# 1-Schematic_Smart_Home.net
KiCad netlist of a schematic drawn in EasyEDA
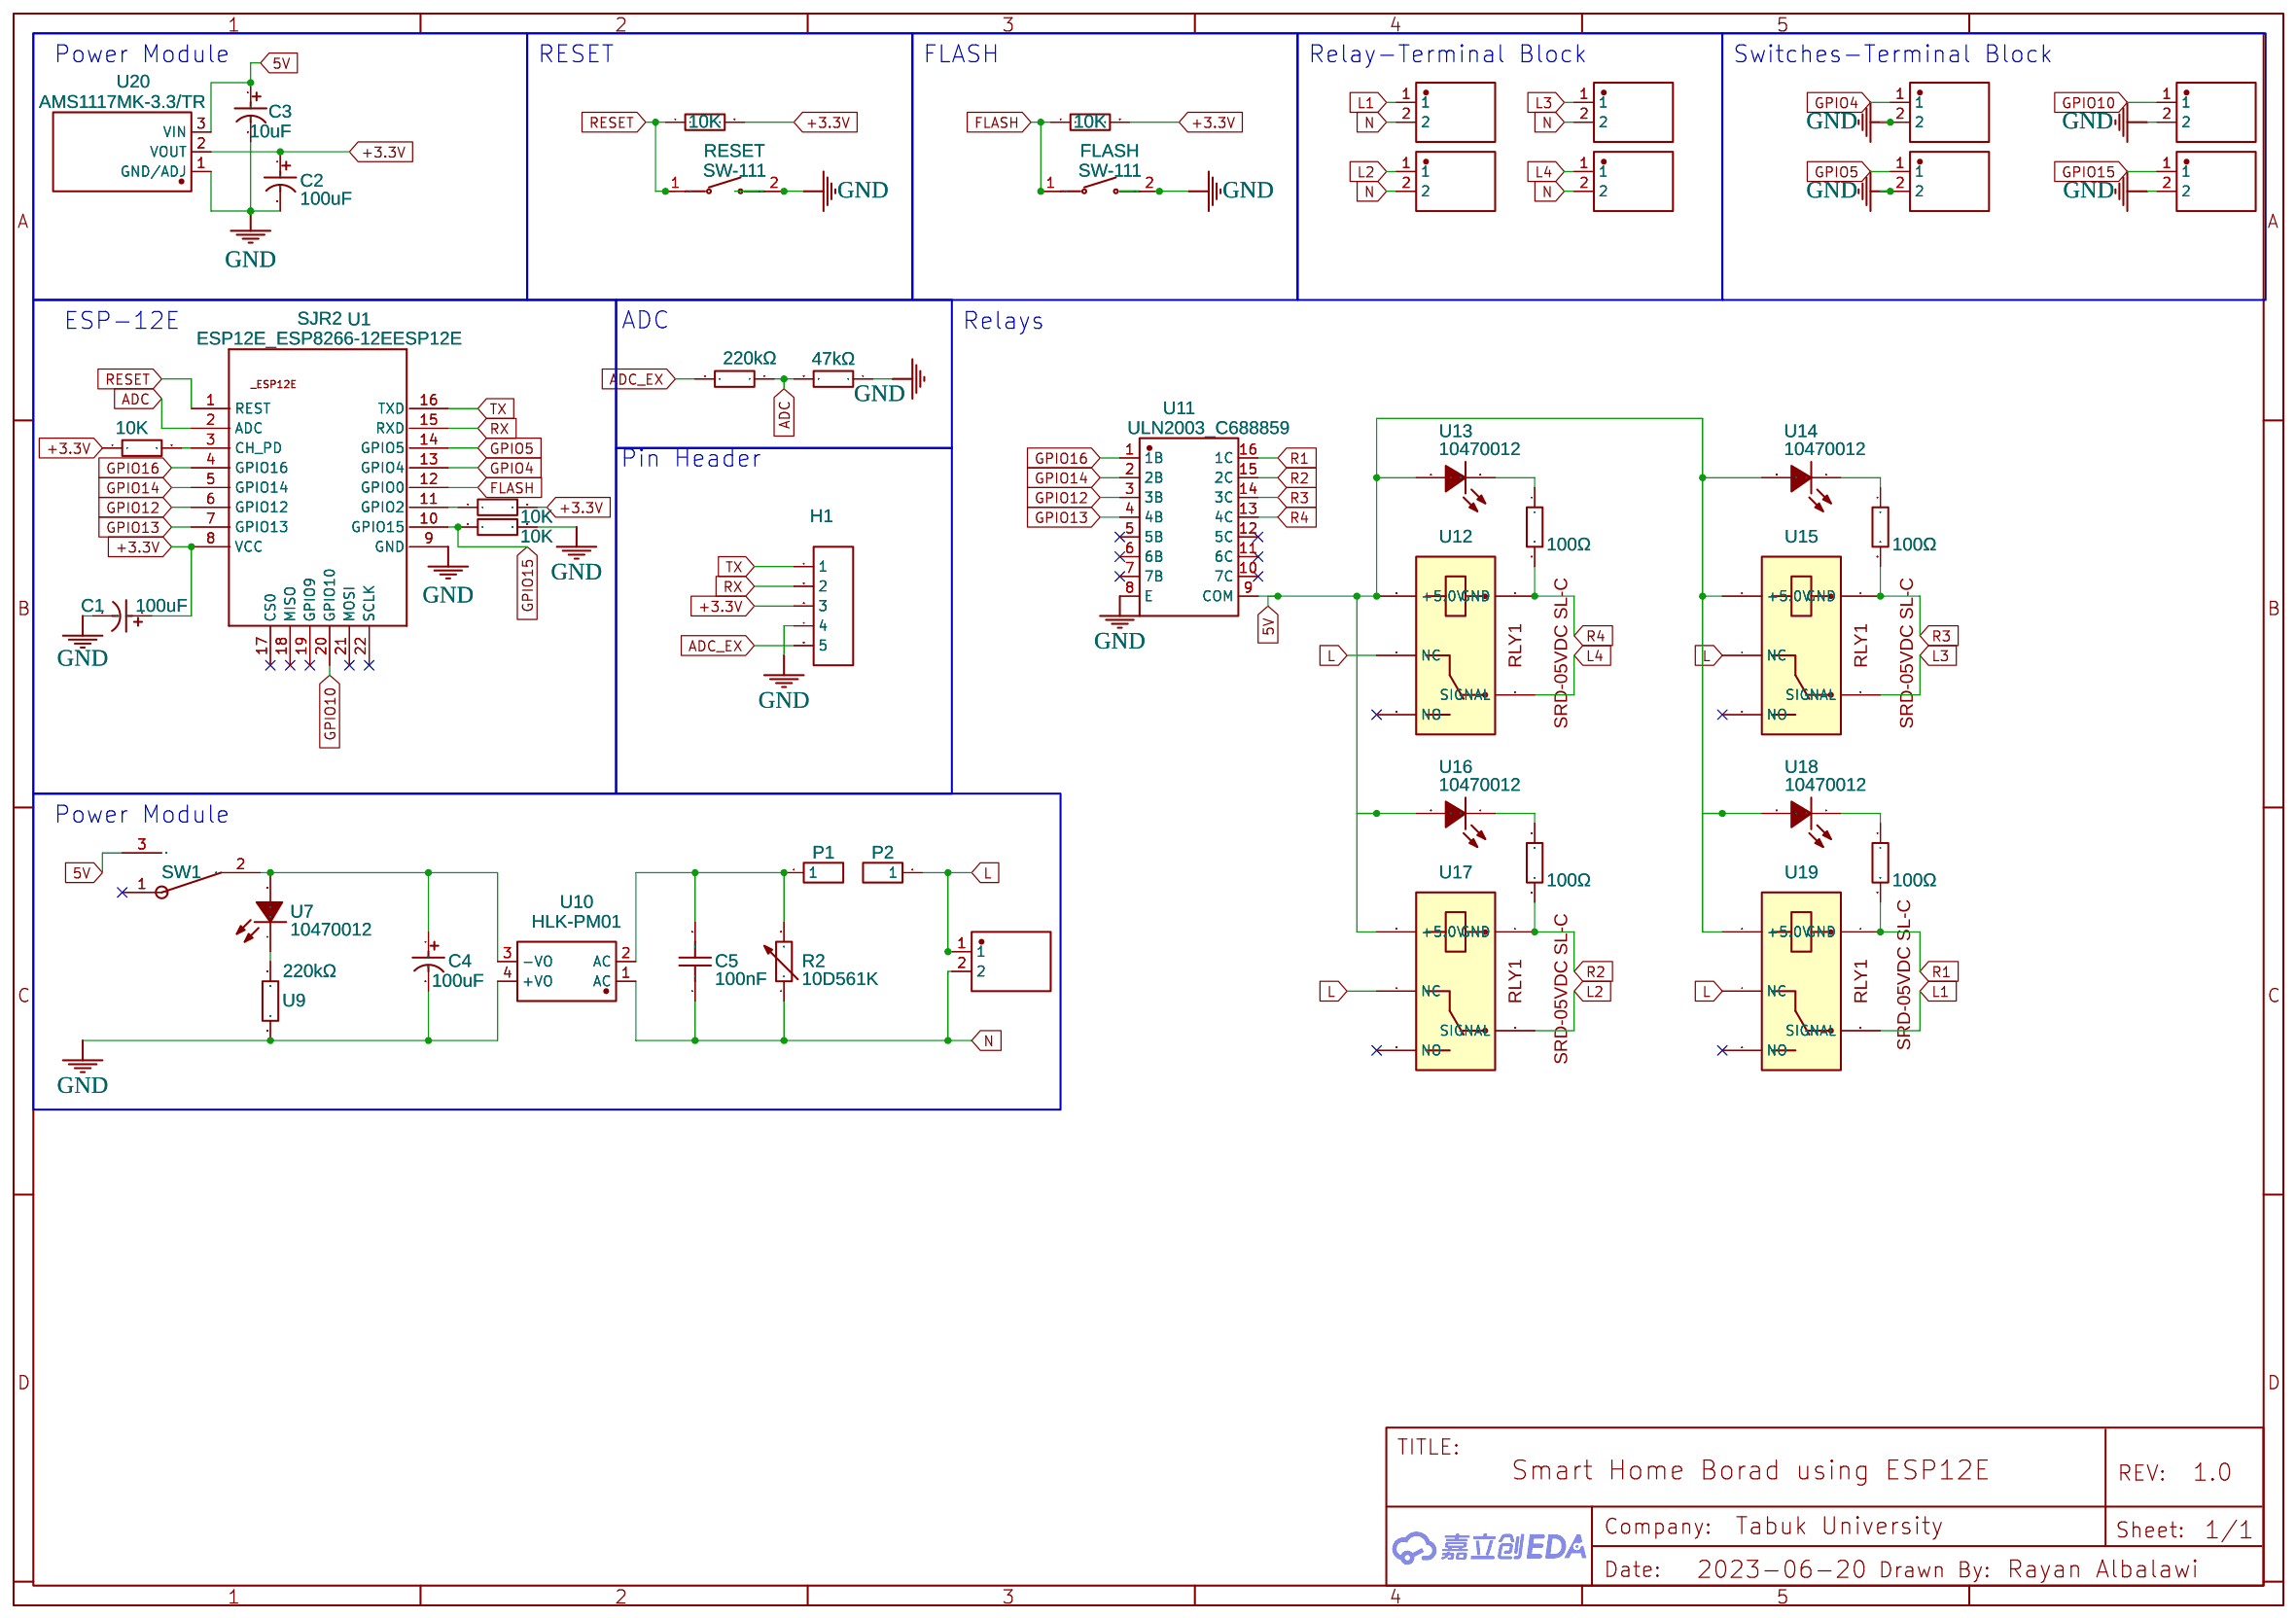
[diagram p0: schematic sheet]

(export (version "E")
  (design (tool "Eeschema 10.0.6"))
  (components
    (comp (ref "C1")
      (value "100uF")
      (fields
        (field (name "BOM_Manufacturer Part") "100uF 35V 6.3*11")
        (field (name "BOM_Supplier Part") "C45076")
      )
      (libsource (lib "") (part "100uF 35V 6.3*11_C45076_1"))
    )
    (comp (ref "C2")
      (value "100uF")
      (fields
        (field (name "BOM_Manufacturer Part") "100uF 35V 6.3*11")
        (field (name "BOM_Supplier Part") "C45076")
      )
      (libsource (lib "") (part "100uF 35V 6.3*11_C45076"))
    )
    (comp (ref "C3")
      (value "10uF")
      (fields
        (field (name "BOM_Manufacturer Part") "100uF 35V 6.3*11")
        (field (name "BOM_Supplier Part") "C45076")
      )
      (libsource (lib "") (part "100uF 35V 6.3*11_C45076"))
    )
    (comp (ref "C4")
      (value "100uF")
      (fields
        (field (name "BOM_Manufacturer Part") "100uF 35V 6.3*11")
        (field (name "BOM_Supplier Part") "C45076")
      )
      (libsource (lib "") (part "100uF 35V 6.3*11_C45076"))
    )
    (comp (ref "C5")
      (value "100nF")
      (fields
        (field (name "BOM_Manufacturer Part") "B32520C3104K000")
        (field (name "BOM_Supplier Part") "C125382")
      )
      (libsource (lib "") (part "B32520C3104K000"))
    )
    (comp (ref "CN1")
      (value "WJ127-5.0-2P_C187897")
      (fields
        (field (name "BOM_Manufacturer Part") "WJ127-5.0-2P")
        (field (name "BOM_Supplier Part") "C187897")
      )
      (libsource (lib "") (part "WJ127-5.0-2P_C187897"))
    )
    (comp (ref "CN2")
      (value "WJ127-5.0-2P_C187897")
      (fields
        (field (name "BOM_Manufacturer Part") "WJ127-5.0-2P")
        (field (name "BOM_Supplier Part") "C187897")
      )
      (libsource (lib "") (part "WJ127-5.0-2P_C187897"))
    )
    (comp (ref "CN3")
      (value "WJ127-5.0-2P_C187897")
      (fields
        (field (name "BOM_Manufacturer Part") "WJ127-5.0-2P")
        (field (name "BOM_Supplier Part") "C187897")
      )
      (libsource (lib "") (part "WJ127-5.0-2P_C187897"))
    )
    (comp (ref "CN4")
      (value "WJ127-5.0-2P_C187897")
      (fields
        (field (name "BOM_Manufacturer Part") "WJ127-5.0-2P")
        (field (name "BOM_Supplier Part") "C187897")
      )
      (libsource (lib "") (part "WJ127-5.0-2P_C187897"))
    )
    (comp (ref "CN5")
      (value "WJ127-5.0-2P_C187897")
      (fields
        (field (name "BOM_Manufacturer Part") "WJ127-5.0-2P")
        (field (name "BOM_Supplier Part") "C187897")
      )
      (libsource (lib "") (part "WJ127-5.0-2P_C187897"))
    )
    (comp (ref "CN6")
      (value "WJ127-5.0-2P_C187897")
      (fields
        (field (name "BOM_Manufacturer Part") "WJ127-5.0-2P")
        (field (name "BOM_Supplier Part") "C187897")
      )
      (libsource (lib "") (part "WJ127-5.0-2P_C187897"))
    )
    (comp (ref "CN7")
      (value "WJ127-5.0-2P_C187897")
      (fields
        (field (name "BOM_Manufacturer Part") "WJ127-5.0-2P")
        (field (name "BOM_Supplier Part") "C187897")
      )
      (libsource (lib "") (part "WJ127-5.0-2P_C187897"))
    )
    (comp (ref "CN8")
      (value "WJ127-5.0-2P_C187897")
      (fields
        (field (name "BOM_Manufacturer Part") "WJ127-5.0-2P")
        (field (name "BOM_Supplier Part") "C187897")
      )
      (libsource (lib "") (part "WJ127-5.0-2P_C187897"))
    )
    (comp (ref "CN9")
      (value "WJ127-5.0-2P_C187897")
      (fields
        (field (name "BOM_Manufacturer Part") "WJ127-5.0-2P")
        (field (name "BOM_Supplier Part") "C187897")
      )
      (libsource (lib "") (part "WJ127-5.0-2P_C187897"))
    )
    (comp (ref "FLASH")
      (value "SW-111")
      (fields (field (name "BOM_Supplier Part") "C294475"))
      (libsource (lib "") (part "SW-111"))
    )
    (comp (ref "H1")
      (value "Header-Female-2.54_1x5")
      (fields (field (name "BOM_Manufacturer Part") "2.54-1*5P母") (field (name "BOM_Supplier Part") "C50950"))
      (libsource (lib "") (part "Header-Female-2.54_1x5"))
    )
    (comp (ref "P1")
      (value "Header-Male-2.54_1x1")
      (fields (field (name "BOM_Manufacturer Part") "2.54-1*1P针") (field (name "BOM_Supplier Part") "C81276"))
      (libsource (lib "") (part "Header-Male-2.54_1x1"))
    )
    (comp (ref "P2")
      (value "Header-Male-2.54_1x1")
      (fields (field (name "BOM_Manufacturer Part") "2.54-1*1P针") (field (name "BOM_Supplier Part") "C81276"))
      (libsource (lib "") (part "Header-Male-2.54_1x1_1"))
    )
    (comp (ref "R1")
      (value "47kΩ")
      (fields
        (field (name "BOM_Manufacturer Part") "MOF2WS-47KΩ±5% T")
        (field (name "BOM_Supplier Part") "C121703")
      )
      (libsource (lib "") (part "MOF2WS-47KΩ±5% T_1"))
    )
    (comp (ref "R2")
      (value "10D561K")
      (fields (field (name "BOM_Supplier Part") "C113236"))
      (libsource (lib "") (part "10D561K"))
    )
    (comp (ref "R3")
      (value "100Ω")
      (fields
        (field (name "BOM_Manufacturer Part") "MOF2WS-47KΩ±5% T")
        (field (name "BOM_Supplier Part") "C121703")
      )
      (libsource (lib "") (part "MOF2WS-47KΩ±5% T"))
    )
    (comp (ref "R4")
      (value "100Ω")
      (fields
        (field (name "BOM_Manufacturer Part") "MOF2WS-47KΩ±5% T")
        (field (name "BOM_Supplier Part") "C121703")
      )
      (libsource (lib "") (part "MOF2WS-47KΩ±5% T"))
    )
    (comp (ref "R5")
      (value "100Ω")
      (fields
        (field (name "BOM_Manufacturer Part") "MOF2WS-47KΩ±5% T")
        (field (name "BOM_Supplier Part") "C121703")
      )
      (libsource (lib "") (part "MOF2WS-47KΩ±5% T"))
    )
    (comp (ref "R6")
      (value "100Ω")
      (fields
        (field (name "BOM_Manufacturer Part") "MOF2WS-47KΩ±5% T")
        (field (name "BOM_Supplier Part") "C121703")
      )
      (libsource (lib "") (part "MOF2WS-47KΩ±5% T"))
    )
    (comp (ref "RESET")
      (value "SW-111")
      (fields (field (name "BOM_Supplier Part") "C294475"))
      (libsource (lib "") (part "SW-111_1"))
    )
    (comp (ref "SJR2")
      (value "ESP12E_ESP8266-12EESP12E")
      (libsource (lib "") (part "ESP12E_ESP8266-12EESP12E"))
    )
    (comp (ref "SW1")
      (value "EG1218")
      (fields (field (name "BOM_Supplier Part") "C273394"))
      (libsource (lib "") (part "EG1218"))
    )
    (comp (ref "U1")
      (value "10K")
      (fields
        (field (name "BOM_Manufacturer Part") "B3950-10K 1%")
        (field (name "BOM_Supplier Part") "C9900005609")
      )
      (libsource (lib "") (part "B3950-10K 1%"))
    )
    (comp (ref "U3")
      (value "10K")
      (fields
        (field (name "BOM_Manufacturer Part") "B3950-10K 1%")
        (field (name "BOM_Supplier Part") "C9900005609")
      )
      (libsource (lib "") (part "B3950-10K 1%"))
    )
    (comp (ref "U4")
      (value "10K")
      (fields
        (field (name "BOM_Manufacturer Part") "B3950-10K 1%")
        (field (name "BOM_Supplier Part") "C9900005609")
      )
      (libsource (lib "") (part "B3950-10K 1%"))
    )
    (comp (ref "U5")
      (value "10K")
      (fields
        (field (name "BOM_Manufacturer Part") "B3950-10K 1%")
        (field (name "BOM_Supplier Part") "C9900005609")
      )
      (libsource (lib "") (part "B3950-10K 1%"))
    )
    (comp (ref "U6")
      (value "10K")
      (fields
        (field (name "BOM_Manufacturer Part") "B3950-10K 1%")
        (field (name "BOM_Supplier Part") "C9900005609")
      )
      (libsource (lib "") (part "B3950-10K 1%"))
    )
    (comp (ref "U7")
      (value "10470012")
      (fields (field (name "BOM_Supplier Part") "C9900018803"))
      (libsource (lib "") (part "10470012_1"))
    )
    (comp (ref "U8")
      (value "220kΩ")
      (fields
        (field (name "BOM_Manufacturer Part") "MOF3WS-100KΩ±5% T")
        (field (name "BOM_Supplier Part") "C121880")
      )
      (libsource (lib "") (part "MOF3WS-100KΩ±5% T"))
    )
    (comp (ref "U9")
      (value "220kΩ")
      (fields
        (field (name "BOM_Manufacturer Part") "MOF3WS-100KΩ±5% T")
        (field (name "BOM_Supplier Part") "C121880")
      )
      (libsource (lib "") (part "MOF3WS-100KΩ±5% T_1"))
    )
    (comp (ref "U10")
      (value "HLK-PM01")
      (fields (field (name "BOM_Supplier Part") "C209903"))
      (libsource (lib "") (part "HLK-PM01"))
    )
    (comp (ref "U11")
      (value "ULN2003_C688859")
      (fields (field (name "BOM_Manufacturer Part") "ULN2003") (field (name "BOM_Supplier Part") "C688859"))
      (libsource (lib "") (part "ULN2003_C688859"))
    )
    (comp (ref "U12")
      (value "SRD-05VDC SL-C BY JMAD COPY")
      (fields (field (name "BOM_Supplier Part") "SRD-05VDC SL-C"))
      (libsource (lib "") (part "SRD-05VDC SL-C BY JMAD COPY_1"))
    )
    (comp (ref "U13")
      (value "10470012")
      (fields (field (name "BOM_Supplier Part") "C9900018803"))
      (libsource (lib "") (part "10470012"))
    )
    (comp (ref "U14")
      (value "10470012")
      (fields (field (name "BOM_Supplier Part") "C9900018803"))
      (libsource (lib "") (part "10470012"))
    )
    (comp (ref "U15")
      (value "SRD-05VDC SL-C BY JMAD COPY")
      (fields (field (name "BOM_Supplier Part") "SRD-05VDC SL-C"))
      (libsource (lib "") (part "SRD-05VDC SL-C BY JMAD COPY_1"))
    )
    (comp (ref "U16")
      (value "10470012")
      (fields (field (name "BOM_Supplier Part") "C9900018803"))
      (libsource (lib "") (part "10470012"))
    )
    (comp (ref "U17")
      (value "SRD-05VDC SL-C BY JMAD COPY")
      (fields (field (name "BOM_Supplier Part") "SRD-05VDC SL-C"))
      (libsource (lib "") (part "SRD-05VDC SL-C BY JMAD COPY_1"))
    )
    (comp (ref "U18")
      (value "10470012")
      (fields (field (name "BOM_Supplier Part") "C9900018803"))
      (libsource (lib "") (part "10470012"))
    )
    (comp (ref "U19")
      (value "SRD-05VDC SL-C BY JMAD COPY")
      (fields (field (name "BOM_Supplier Part") "SRD-05VDC SL-C"))
      (libsource (lib "") (part "SRD-05VDC SL-C BY JMAD COPY"))
    )
    (comp (ref "U20")
      (value "AMS1117MK-3.3/TR")
      (fields (field (name "BOM_Supplier Part") "C498147"))
      (libsource (lib "") (part "AMS1117MK-3.3/TR"))
    )
  )
  (nets
    (net (code "1") (name "+3.3V") (class "Default")
      (node (ref "C1") (pin "1") (pinfunction "1_1") (pintype "input"))
      (node (ref "C2") (pin "1") (pinfunction "1_1") (pintype "input"))
      (node (ref "H1") (pin "3") (pinfunction "3_3") (pintype "input"))
      (node (ref "SJR2") (pin "8") (pinfunction "VCC_8") (pintype "bidirectional"))
      (node (ref "U1") (pin "1") (pinfunction "1_1") (pintype "unspecified"))
      (node (ref "U20") (pin "2") (pinfunction "VOUT_2") (pintype "unspecified"))
      (node (ref "U3") (pin "2") (pinfunction "2_2") (pintype "unspecified"))
      (node (ref "U5") (pin "2") (pinfunction "2_2") (pintype "unspecified"))
      (node (ref "U6") (pin "2") (pinfunction "2_2") (pintype "unspecified"))
    )
    (net (code "2") (name "5V") (class "Default")
      (node (ref "C3") (pin "1") (pinfunction "1_1") (pintype "input"))
      (node (ref "SW1") (pin "3") (pinfunction "3_3") (pintype "input"))
      (node (ref "U11") (pin "9") (pinfunction "COM_9") (pintype "unspecified"))
      (node (ref "U12") (pin "2") (pinfunction "+5.0V_2") (pintype "passive"))
      (node (ref "U13") (pin "2") (pinfunction "A_2") (pintype "unspecified"))
      (node (ref "U14") (pin "2") (pinfunction "A_2") (pintype "unspecified"))
      (node (ref "U15") (pin "2") (pinfunction "+5.0V_2") (pintype "passive"))
      (node (ref "U16") (pin "2") (pinfunction "A_2") (pintype "unspecified"))
      (node (ref "U17") (pin "2") (pinfunction "+5.0V_2") (pintype "passive"))
      (node (ref "U18") (pin "2") (pinfunction "A_2") (pintype "unspecified"))
      (node (ref "U19") (pin "2") (pinfunction "+5.0V_2") (pintype "passive"))
      (node (ref "U20") (pin "3") (pinfunction "VIN_3") (pintype "unspecified"))
    )
    (net (code "3") (name "ADC") (class "Default")
      (node (ref "R1") (pin "2") (pinfunction "2_2") (pintype "unspecified"))
      (node (ref "SJR2") (pin "2") (pinfunction "ADC_2") (pintype "bidirectional"))
      (node (ref "U8") (pin "1") (pinfunction "1_1") (pintype "unspecified"))
    )
    (net (code "4") (name "ADC_EX") (class "Default")
      (node (ref "H1") (pin "5") (pinfunction "5_5") (pintype "input"))
      (node (ref "U8") (pin "2") (pinfunction "2_2") (pintype "unspecified"))
    )
    (net (code "5") (name "FLASH") (class "Default")
      (node (ref "FLASH") (pin "1") (pinfunction "1_1") (pintype "unspecified"))
      (node (ref "SJR2") (pin "12") (pinfunction "GPIO0_12") (pintype "bidirectional"))
      (node (ref "U6") (pin "1") (pinfunction "1_1") (pintype "unspecified"))
    )
    (net (code "6") (name "GND") (class "Default")
      (node (ref "C1") (pin "2") (pinfunction "2_2") (pintype "input"))
      (node (ref "C2") (pin "2") (pinfunction "2_2") (pintype "input"))
      (node (ref "C3") (pin "2") (pinfunction "2_2") (pintype "input"))
      (node (ref "C4") (pin "2") (pinfunction "2_2") (pintype "input"))
      (node (ref "CN5") (pin "2") (pinfunction "2_2") (pintype "unspecified"))
      (node (ref "CN6") (pin "2") (pinfunction "2_2") (pintype "unspecified"))
      (node (ref "CN7") (pin "2") (pinfunction "2_2") (pintype "unspecified"))
      (node (ref "CN8") (pin "2") (pinfunction "2_2") (pintype "unspecified"))
      (node (ref "FLASH") (pin "2") (pinfunction "2_2") (pintype "unspecified"))
      (node (ref "H1") (pin "4") (pinfunction "4_4") (pintype "input"))
      (node (ref "R1") (pin "1") (pinfunction "1_1") (pintype "unspecified"))
      (node (ref "RESET") (pin "2") (pinfunction "2_2") (pintype "unspecified"))
      (node (ref "SJR2") (pin "9") (pinfunction "GND_9") (pintype "bidirectional"))
      (node (ref "U10") (pin "4") (pinfunction "+VO_4") (pintype "unspecified"))
      (node (ref "U11") (pin "8") (pinfunction "E_8") (pintype "unspecified"))
      (node (ref "U20") (pin "1") (pinfunction "GND/ADJ_1") (pintype "unspecified"))
      (node (ref "U4") (pin "2") (pinfunction "2_2") (pintype "unspecified"))
      (node (ref "U9") (pin "1") (pinfunction "1_1") (pintype "unspecified"))
    )
    (net (code "7") (name "GPIO4") (class "Default")
      (node (ref "CN8") (pin "1") (pinfunction "1_1") (pintype "unspecified"))
      (node (ref "SJR2") (pin "13") (pinfunction "GPIO4_13") (pintype "bidirectional"))
    )
    (net (code "8") (name "GPIO5") (class "Default")
      (node (ref "CN7") (pin "1") (pinfunction "1_1") (pintype "unspecified"))
      (node (ref "SJR2") (pin "14") (pinfunction "GPIO5_14") (pintype "bidirectional"))
    )
    (net (code "9") (name "GPIO10") (class "Default")
      (node (ref "CN6") (pin "1") (pinfunction "1_1") (pintype "unspecified"))
      (node (ref "SJR2") (pin "20") (pinfunction "GPIO10_20") (pintype "bidirectional"))
    )
    (net (code "10") (name "GPIO12") (class "Default")
      (node (ref "SJR2") (pin "6") (pinfunction "GPIO12_6") (pintype "bidirectional"))
      (node (ref "U11") (pin "3") (pinfunction "3B_3") (pintype "unspecified"))
    )
    (net (code "11") (name "GPIO13") (class "Default")
      (node (ref "SJR2") (pin "7") (pinfunction "GPIO13_7") (pintype "bidirectional"))
      (node (ref "U11") (pin "4") (pinfunction "4B_4") (pintype "unspecified"))
    )
    (net (code "12") (name "GPIO14") (class "Default")
      (node (ref "SJR2") (pin "5") (pinfunction "GPIO14_5") (pintype "bidirectional"))
      (node (ref "U11") (pin "2") (pinfunction "2B_2") (pintype "unspecified"))
    )
    (net (code "13") (name "GPIO15") (class "Default")
      (node (ref "CN5") (pin "1") (pinfunction "1_1") (pintype "unspecified"))
      (node (ref "SJR2") (pin "10") (pinfunction "GPIO15_10") (pintype "bidirectional"))
      (node (ref "U4") (pin "1") (pinfunction "1_1") (pintype "unspecified"))
    )
    (net (code "14") (name "GPIO16") (class "Default")
      (node (ref "SJR2") (pin "4") (pinfunction "GPIO16_4") (pintype "bidirectional"))
      (node (ref "U11") (pin "1") (pinfunction "1B_1") (pintype "unspecified"))
    )
    (net (code "15") (name "L") (class "Default")
      (node (ref "CN9") (pin "1") (pinfunction "1_1") (pintype "unspecified"))
      (node (ref "P2") (pin "1") (pinfunction "1_1") (pintype "input"))
      (node (ref "U12") (pin "4") (pinfunction "NC_4") (pintype "input"))
      (node (ref "U15") (pin "4") (pinfunction "NC_4") (pintype "input"))
      (node (ref "U17") (pin "4") (pinfunction "NC_4") (pintype "input"))
      (node (ref "U19") (pin "4") (pinfunction "NC_4") (pintype "input"))
    )
    (net (code "16") (name "L1") (class "Default")
      (node (ref "CN1") (pin "1") (pinfunction "1_1") (pintype "unspecified"))
      (node (ref "U19") (pin "5") (pinfunction "SIGNAL_5") (pintype "output"))
    )
    (net (code "17") (name "L2") (class "Default")
      (node (ref "CN2") (pin "1") (pinfunction "1_1") (pintype "unspecified"))
      (node (ref "U17") (pin "5") (pinfunction "SIGNAL_5") (pintype "output"))
    )
    (net (code "18") (name "L3") (class "Default")
      (node (ref "CN3") (pin "1") (pinfunction "1_1") (pintype "unspecified"))
      (node (ref "U15") (pin "5") (pinfunction "SIGNAL_5") (pintype "output"))
    )
    (net (code "19") (name "L4") (class "Default")
      (node (ref "CN4") (pin "1") (pinfunction "1_1") (pintype "unspecified"))
      (node (ref "U12") (pin "5") (pinfunction "SIGNAL_5") (pintype "output"))
    )
    (net (code "20") (name "N") (class "Default")
      (node (ref "C5") (pin "1") (pinfunction "1_1") (pintype "unspecified"))
      (node (ref "CN1") (pin "2") (pinfunction "2_2") (pintype "unspecified"))
      (node (ref "CN2") (pin "2") (pinfunction "2_2") (pintype "unspecified"))
      (node (ref "CN3") (pin "2") (pinfunction "2_2") (pintype "unspecified"))
      (node (ref "CN4") (pin "2") (pinfunction "2_2") (pintype "unspecified"))
      (node (ref "CN9") (pin "2") (pinfunction "2_2") (pintype "unspecified"))
      (node (ref "R2") (pin "1") (pinfunction "1_1") (pintype "unspecified"))
      (node (ref "U10") (pin "1") (pinfunction "AC_1") (pintype "unspecified"))
    )
    (net (code "21") (name "Net-(C5-Pad2)") (class "Default")
      (node (ref "C5") (pin "2") (pinfunction "2_2") (pintype "unspecified"))
      (node (ref "P1") (pin "1") (pinfunction "1_1") (pintype "input"))
      (node (ref "R2") (pin "2") (pinfunction "2_2") (pintype "unspecified"))
      (node (ref "U10") (pin "2") (pinfunction "AC_2") (pintype "unspecified"))
    )
    (net (code "22") (name "Net-(SJR2-CH_PD)") (class "Default")
      (node (ref "SJR2") (pin "3") (pinfunction "CH_PD_3") (pintype "bidirectional"))
      (node (ref "U1") (pin "2") (pinfunction "2_2") (pintype "unspecified"))
    )
    (net (code "23") (name "Net-(SJR2-GPIO2)") (class "Default")
      (node (ref "SJR2") (pin "11") (pinfunction "GPIO2_11") (pintype "bidirectional"))
      (node (ref "U3") (pin "1") (pinfunction "1_1") (pintype "unspecified"))
    )
    (net (code "24") (name "Net-(U7-K)") (class "Default")
      (node (ref "U7") (pin "1") (pinfunction "K_1") (pintype "unspecified"))
      (node (ref "U9") (pin "2") (pinfunction "2_2") (pintype "unspecified"))
    )
    (net (code "25") (name "Net-(U10--VO)") (class "Default")
      (node (ref "C4") (pin "1") (pinfunction "1_1") (pintype "input"))
      (node (ref "SW1") (pin "2") (pinfunction "2_2") (pintype "input"))
      (node (ref "U10") (pin "3") (pinfunction "-VO_3") (pintype "unspecified"))
      (node (ref "U7") (pin "2") (pinfunction "A_2") (pintype "unspecified"))
    )
    (net (code "26") (name "Net-(U13-K)") (class "Default")
      (node (ref "R3") (pin "1") (pinfunction "1_1") (pintype "unspecified"))
      (node (ref "U13") (pin "1") (pinfunction "K_1") (pintype "unspecified"))
    )
    (net (code "27") (name "Net-(U14-K)") (class "Default")
      (node (ref "R4") (pin "1") (pinfunction "1_1") (pintype "unspecified"))
      (node (ref "U14") (pin "1") (pinfunction "K_1") (pintype "unspecified"))
    )
    (net (code "28") (name "Net-(U16-K)") (class "Default")
      (node (ref "R5") (pin "1") (pinfunction "1_1") (pintype "unspecified"))
      (node (ref "U16") (pin "1") (pinfunction "K_1") (pintype "unspecified"))
    )
    (net (code "29") (name "Net-(U18-K)") (class "Default")
      (node (ref "R6") (pin "1") (pinfunction "1_1") (pintype "unspecified"))
      (node (ref "U18") (pin "1") (pinfunction "K_1") (pintype "unspecified"))
    )
    (net (code "30") (name "R1") (class "Default")
      (node (ref "R6") (pin "2") (pinfunction "2_2") (pintype "unspecified"))
      (node (ref "U11") (pin "16") (pinfunction "1C_16") (pintype "unspecified"))
      (node (ref "U19") (pin "1") (pinfunction "GND_1") (pintype "passive"))
    )
    (net (code "31") (name "R2") (class "Default")
      (node (ref "R5") (pin "2") (pinfunction "2_2") (pintype "unspecified"))
      (node (ref "U11") (pin "15") (pinfunction "2C_15") (pintype "unspecified"))
      (node (ref "U17") (pin "1") (pinfunction "GND_1") (pintype "passive"))
    )
    (net (code "32") (name "R3") (class "Default")
      (node (ref "R4") (pin "2") (pinfunction "2_2") (pintype "unspecified"))
      (node (ref "U11") (pin "14") (pinfunction "3C_14") (pintype "unspecified"))
      (node (ref "U15") (pin "1") (pinfunction "GND_1") (pintype "passive"))
    )
    (net (code "33") (name "R4") (class "Default")
      (node (ref "R3") (pin "2") (pinfunction "2_2") (pintype "unspecified"))
      (node (ref "U11") (pin "13") (pinfunction "4C_13") (pintype "unspecified"))
      (node (ref "U12") (pin "1") (pinfunction "GND_1") (pintype "passive"))
    )
    (net (code "34") (name "RESET") (class "Default")
      (node (ref "RESET") (pin "1") (pinfunction "1_1") (pintype "unspecified"))
      (node (ref "SJR2") (pin "1") (pinfunction "REST_1") (pintype "bidirectional"))
      (node (ref "U5") (pin "1") (pinfunction "1_1") (pintype "unspecified"))
    )
    (net (code "35") (name "RX") (class "Default")
      (node (ref "H1") (pin "2") (pinfunction "2_2") (pintype "input"))
      (node (ref "SJR2") (pin "15") (pinfunction "RXD_15") (pintype "bidirectional"))
    )
    (net (code "36") (name "TX") (class "Default")
      (node (ref "H1") (pin "1") (pinfunction "1_1") (pintype "input"))
      (node (ref "SJR2") (pin "16") (pinfunction "TXD_16") (pintype "bidirectional"))
    )
    (net (code "37") (name "unconnected-(SJR2-CS0-Pad17)") (class "Default")
      (node (ref "SJR2") (pin "17") (pinfunction "CS0_17") (pintype "bidirectional+no_connect"))
    )
    (net (code "38") (name "unconnected-(SJR2-GPIO9-Pad19)") (class "Default")
      (node (ref "SJR2") (pin "19") (pinfunction "GPIO9_19") (pintype "bidirectional+no_connect"))
    )
    (net (code "39") (name "unconnected-(SJR2-MISO-Pad18)") (class "Default")
      (node (ref "SJR2") (pin "18") (pinfunction "MISO_18") (pintype "bidirectional+no_connect"))
    )
    (net (code "40") (name "unconnected-(SJR2-MOSI-Pad21)") (class "Default")
      (node (ref "SJR2") (pin "21") (pinfunction "MOSI_21") (pintype "bidirectional+no_connect"))
    )
    (net (code "41") (name "unconnected-(SJR2-SCLK-Pad22)") (class "Default")
      (node (ref "SJR2") (pin "22") (pinfunction "SCLK_22") (pintype "bidirectional+no_connect"))
    )
    (net (code "42") (name "unconnected-(SW1-Pad1)") (class "Default")
      (node (ref "SW1") (pin "1") (pinfunction "1_1") (pintype "input+no_connect"))
    )
    (net (code "43") (name "unconnected-(U11-5B-Pad5)") (class "Default")
      (node (ref "U11") (pin "5") (pinfunction "5B_5") (pintype "unspecified+no_connect"))
    )
    (net (code "44") (name "unconnected-(U11-5C-Pad12)") (class "Default")
      (node (ref "U11") (pin "12") (pinfunction "5C_12") (pintype "unspecified+no_connect"))
    )
    (net (code "45") (name "unconnected-(U11-6B-Pad6)") (class "Default")
      (node (ref "U11") (pin "6") (pinfunction "6B_6") (pintype "unspecified+no_connect"))
    )
    (net (code "46") (name "unconnected-(U11-6C-Pad11)") (class "Default")
      (node (ref "U11") (pin "11") (pinfunction "6C_11") (pintype "unspecified+no_connect"))
    )
    (net (code "47") (name "unconnected-(U11-7B-Pad7)") (class "Default")
      (node (ref "U11") (pin "7") (pinfunction "7B_7") (pintype "unspecified+no_connect"))
    )
    (net (code "48") (name "unconnected-(U11-7C-Pad10)") (class "Default")
      (node (ref "U11") (pin "10") (pinfunction "7C_10") (pintype "unspecified+no_connect"))
    )
    (net (code "49") (name "unconnected-(U12-NO-Pad3)") (class "Default")
      (node (ref "U12") (pin "3") (pinfunction "NO_3") (pintype "output+no_connect"))
    )
    (net (code "50") (name "unconnected-(U15-NO-Pad3)") (class "Default")
      (node (ref "U15") (pin "3") (pinfunction "NO_3") (pintype "output+no_connect"))
    )
    (net (code "51") (name "unconnected-(U17-NO-Pad3)") (class "Default")
      (node (ref "U17") (pin "3") (pinfunction "NO_3") (pintype "output+no_connect"))
    )
    (net (code "52") (name "unconnected-(U19-NO-Pad3)") (class "Default")
      (node (ref "U19") (pin "3") (pinfunction "NO_3") (pintype "output+no_connect"))
    )
  )
)
